# untitled.net
KiCad netlist of a schematic drawn in EAGLE
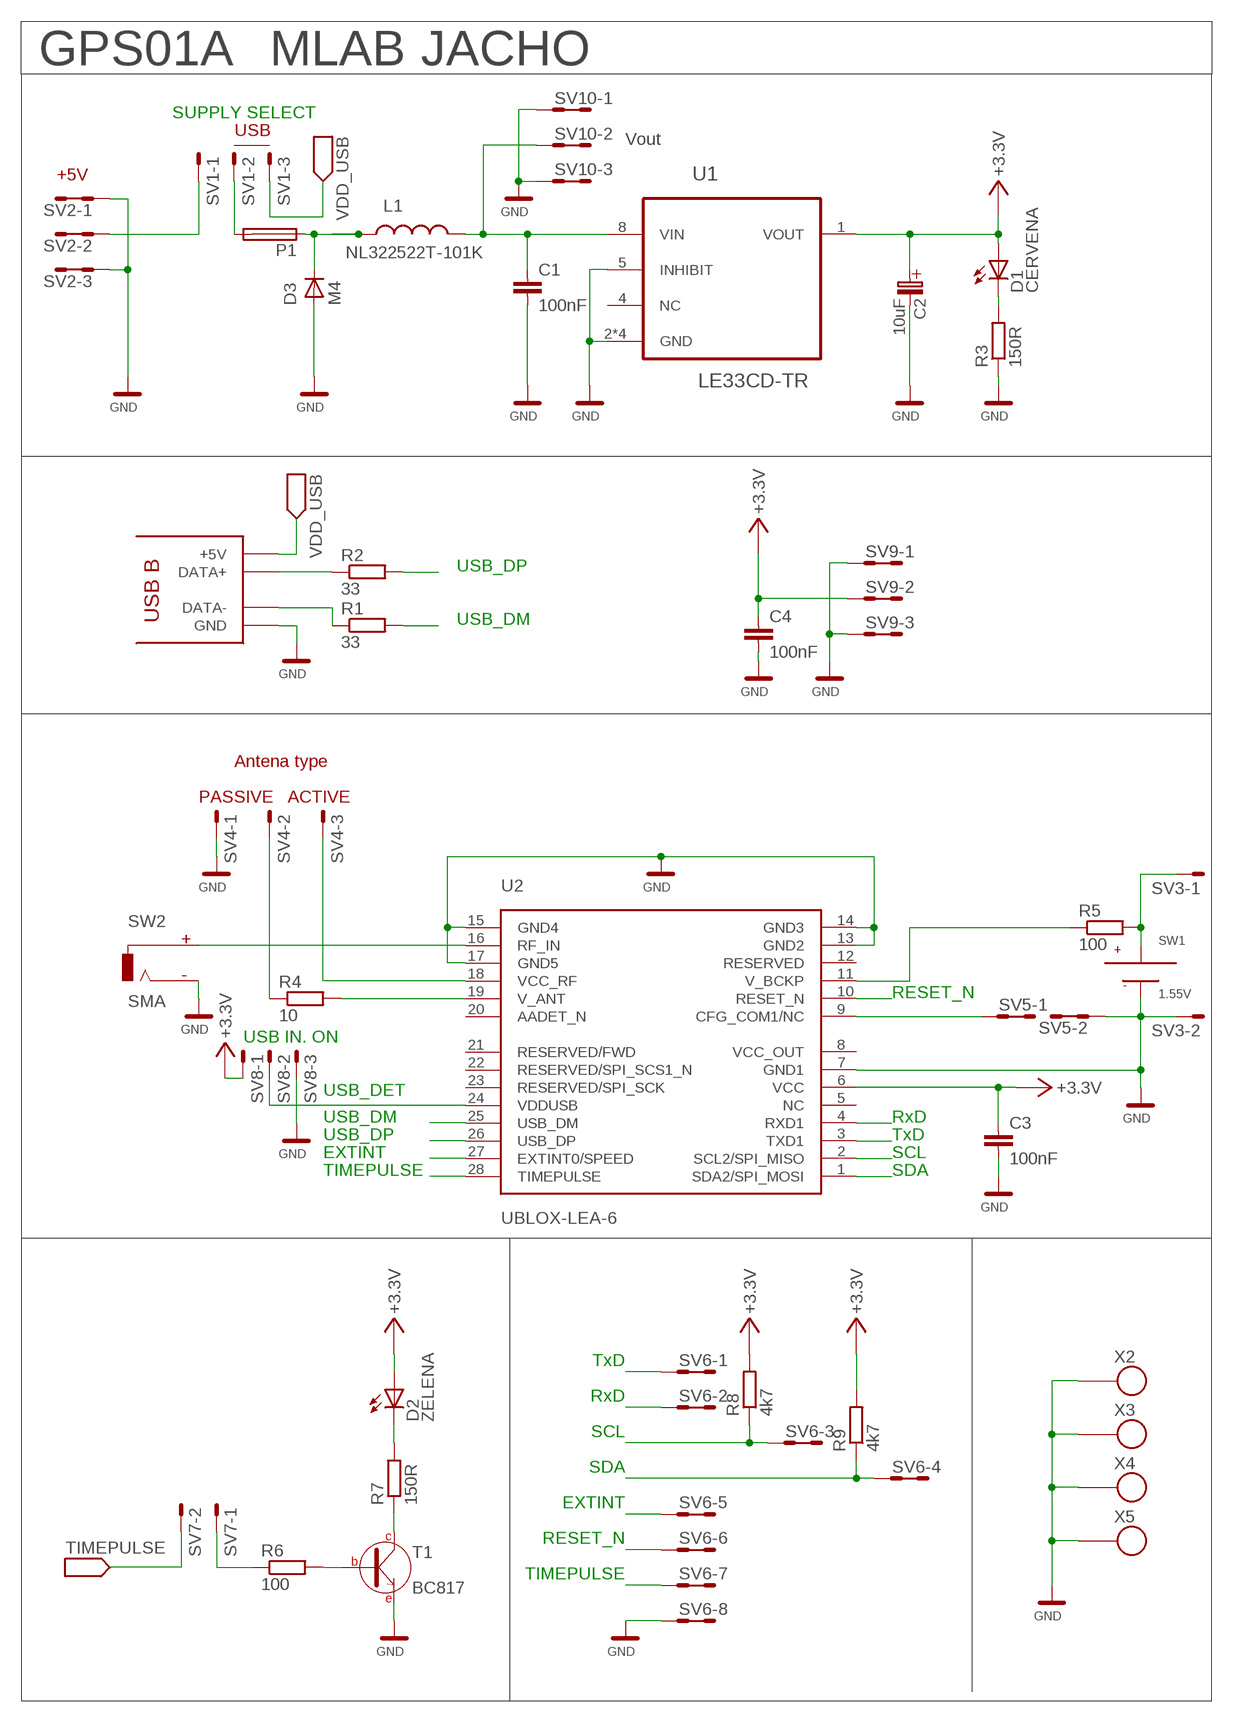
[diagram p0: schematic, sheet 1]

(export (version "E")
  (design (tool "Eeschema 10.0.6"))
  (components
    (comp (ref "C1")
      (value "100nF")
      (footprint "eagle-import:C0805")
      (libsource (lib "eagle-import") (part "C0805"))
    )
    (comp (ref "C2") (value "10uF") (footprint "eagle-import:B") (libsource (lib "eagle-import") (part "B")))
    (comp (ref "C3")
      (value "100nF")
      (footprint "eagle-import:C0805")
      (libsource (lib "eagle-import") (part "C0805"))
    )
    (comp (ref "C4")
      (value "100nF")
      (footprint "eagle-import:C0805")
      (libsource (lib "eagle-import") (part "C0805"))
    )
    (comp (ref "D1")
      (value "CERVENA")
      (footprint "eagle-import:1206")
      (libsource (lib "eagle-import") (part "LED1206"))
    )
    (comp (ref "D2")
      (value "ZELENA")
      (footprint "eagle-import:1206")
      (libsource (lib "eagle-import") (part "LED1206"))
    )
    (comp (ref "D3")
      (value "M4")
      (footprint "eagle-import:SMA")
      (libsource (lib "eagle-import") (part "D-OB.SMA"))
    )
    (comp (ref "L1")
      (value "NL322522T-101K")
      (footprint "eagle-import:1210")
      (libsource (lib "eagle-import") (part "L1210"))
    )
    (comp (ref "P1")
      (value "POJISTKA_1812")
      (footprint "eagle-import:1812")
      (libsource (lib "eagle-import") (part "POJISTKA_1812"))
    )
    (comp (ref "R1")
      (value "33")
      (footprint "eagle-import:0805")
      (libsource (lib "eagle-import") (part "R0805"))
    )
    (comp (ref "R2")
      (value "33")
      (footprint "eagle-import:0805")
      (libsource (lib "eagle-import") (part "R0805"))
    )
    (comp (ref "R3")
      (value "150R")
      (footprint "eagle-import:0805")
      (libsource (lib "eagle-import") (part "R0805"))
    )
    (comp (ref "R4")
      (value "10")
      (footprint "eagle-import:0805")
      (libsource (lib "eagle-import") (part "R0805"))
    )
    (comp (ref "R5")
      (value "100")
      (footprint "eagle-import:0805")
      (libsource (lib "eagle-import") (part "R0805"))
    )
    (comp (ref "R6")
      (value "100")
      (footprint "eagle-import:0805")
      (libsource (lib "eagle-import") (part "R0805"))
    )
    (comp (ref "R7")
      (value "150R")
      (footprint "eagle-import:0805")
      (libsource (lib "eagle-import") (part "R0805"))
    )
    (comp (ref "R8")
      (value "4k7")
      (footprint "eagle-import:0805")
      (libsource (lib "eagle-import") (part "R0805"))
    )
    (comp (ref "R9")
      (value "4k7")
      (footprint "eagle-import:0805")
      (libsource (lib "eagle-import") (part "R0805"))
    )
    (comp (ref "SV1")
      (value "MA03-1")
      (footprint "eagle-import:MA03-1")
      (libsource (lib "eagle-import") (part "MA03-1"))
    )
    (comp (ref "SV2")
      (value "MA03-2")
      (footprint "eagle-import:MA03-2")
      (libsource (lib "eagle-import") (part "MA03-2"))
    )
    (comp (ref "SV3")
      (value "MA02-1")
      (footprint "eagle-import:MA02-1")
      (libsource (lib "eagle-import") (part "MA02-1"))
    )
    (comp (ref "SV4")
      (value "MA03-1")
      (footprint "eagle-import:MA03-1")
      (libsource (lib "eagle-import") (part "MA03-1"))
    )
    (comp (ref "SV5")
      (value "MA02-2")
      (footprint "eagle-import:MA02-2")
      (libsource (lib "eagle-import") (part "MA02-2"))
    )
    (comp (ref "SV6")
      (value "MA08-2")
      (footprint "eagle-import:MA08-2")
      (libsource (lib "eagle-import") (part "MA08-2"))
    )
    (comp (ref "SV7")
      (value "MA02-1")
      (footprint "eagle-import:MA02-1")
      (libsource (lib "eagle-import") (part "MA02-1"))
    )
    (comp (ref "SV8")
      (value "MA03-1")
      (footprint "eagle-import:MA03-1")
      (libsource (lib "eagle-import") (part "MA03-1"))
    )
    (comp (ref "SV9")
      (value "MA03-2")
      (footprint "eagle-import:MA03-2")
      (libsource (lib "eagle-import") (part "MA03-2"))
    )
    (comp (ref "SV10")
      (value "MA03-2")
      (footprint "eagle-import:MA03-2")
      (libsource (lib "eagle-import") (part "MA03-2"))
    )
    (comp (ref "SW1")
      (value "1.55V")
      (footprint "eagle-import:BAT6MM8")
      (libsource (lib "eagle-import") (part "BAT6MM8"))
    )
    (comp (ref "SW2")
      (value "SMA")
      (footprint "eagle-import:SMA")
      (libsource (lib "eagle-import") (part "SMA"))
    )
    (comp (ref "T1")
      (value "BC817")
      (footprint "eagle-import:SOT23")
      (libsource (lib "eagle-import") (part "BC817"))
    )
    (comp (ref "U1")
      (value "LE33CD-TR")
      (footprint "eagle-import:SOIC127P600X175-8N")
      (libsource (lib "eagle-import") (part "LE33CD-TR"))
    )
    (comp (ref "U2")
      (value "UBLOX-LEA-6")
      (footprint "eagle-import:UBLOX-LEA-6")
      (libsource (lib "eagle-import") (part "UBLOX-LEA-6"))
    )
    (comp (ref "X1")
      (value "USB_B")
      (footprint "eagle-import:USB_B")
      (libsource (lib "eagle-import") (part "USB_B"))
    )
    (comp (ref "X2")
      (value "SROUB3M")
      (footprint "eagle-import:SROUB3M")
      (libsource (lib "eagle-import") (part "SROUB3M"))
    )
    (comp (ref "X3")
      (value "SROUB3M")
      (footprint "eagle-import:SROUB3M")
      (libsource (lib "eagle-import") (part "SROUB3M"))
    )
    (comp (ref "X4")
      (value "SROUB3M")
      (footprint "eagle-import:SROUB3M")
      (libsource (lib "eagle-import") (part "SROUB3M"))
    )
    (comp (ref "X5")
      (value "SROUB3M")
      (footprint "eagle-import:SROUB3M")
      (libsource (lib "eagle-import") (part "SROUB3M"))
    )
  )
  (nets
    (net (code "1") (name "+3.3V") (class "Default")
      (node (ref "C2") (pin "+") (pinfunction "C_EL+_+") (pintype "passive"))
      (node (ref "C3") (pin "1") (pinfunction "1_1") (pintype "passive"))
      (node (ref "C4") (pin "1") (pinfunction "1_1") (pintype "passive"))
      (node (ref "D1") (pin "A") (pinfunction "A_A") (pintype "passive"))
      (node (ref "D2") (pin "A") (pinfunction "A_A") (pintype "passive"))
      (node (ref "R8") (pin "2") (pinfunction "2_2") (pintype "passive"))
      (node (ref "R9") (pin "2") (pinfunction "2_2") (pintype "passive"))
      (node (ref "SV8") (pin "1") (pinfunction "P$1_1") (pintype "passive"))
      (node (ref "SV9") (pin "3") (pinfunction "K_3") (pintype "passive"))
      (node (ref "SV9") (pin "4") (pinfunction "K_4") (pintype "passive"))
      (node (ref "U1") (pin "1") (pinfunction "VOUT_1") (pintype "output"))
      (node (ref "U2") (pin "6") (pinfunction "VCC_6") (pintype "bidirectional"))
    )
    (net (code "2") (name "/EXTINT") (class "Default")
      (node (ref "SV6") (pin "10") (pinfunction "K_10") (pintype "passive"))
      (node (ref "SV6") (pin "9") (pinfunction "K_9") (pintype "passive"))
      (node (ref "U2") (pin "27") (pinfunction "EXTINT0/SPEED_27") (pintype "bidirectional"))
    )
    (net (code "3") (name "/RESET_N") (class "Default")
      (node (ref "SV6") (pin "11") (pinfunction "K_11") (pintype "passive"))
      (node (ref "SV6") (pin "12") (pinfunction "K_12") (pintype "passive"))
      (node (ref "U2") (pin "10") (pinfunction "RESET_N_10") (pintype "bidirectional"))
    )
    (net (code "4") (name "/RXD") (class "Default")
      (node (ref "SV6") (pin "3") (pinfunction "K_3") (pintype "passive"))
      (node (ref "SV6") (pin "4") (pinfunction "K_4") (pintype "passive"))
      (node (ref "U2") (pin "4") (pinfunction "RXD1_4") (pintype "bidirectional"))
    )
    (net (code "5") (name "/SCL") (class "Default")
      (node (ref "R8") (pin "1") (pinfunction "1_1") (pintype "passive"))
      (node (ref "SV6") (pin "5") (pinfunction "K_5") (pintype "passive"))
      (node (ref "SV6") (pin "6") (pinfunction "K_6") (pintype "passive"))
      (node (ref "U2") (pin "2") (pinfunction "SCL2/SPI_MISO_2") (pintype "bidirectional"))
    )
    (net (code "6") (name "/SDA") (class "Default")
      (node (ref "R9") (pin "1") (pinfunction "1_1") (pintype "passive"))
      (node (ref "SV6") (pin "7") (pinfunction "K_7") (pintype "passive"))
      (node (ref "SV6") (pin "8") (pinfunction "K_8") (pintype "passive"))
      (node (ref "U2") (pin "1") (pinfunction "SDA2/SPI_MOSI_1") (pintype "bidirectional"))
    )
    (net (code "7") (name "/TIMEPULSE") (class "Default")
      (node (ref "SV6") (pin "13") (pinfunction "K_13") (pintype "passive"))
      (node (ref "SV6") (pin "14") (pinfunction "K_14") (pintype "passive"))
      (node (ref "SV7") (pin "2") (pinfunction "P$1_2") (pintype "passive"))
      (node (ref "U2") (pin "28") (pinfunction "TIMEPULSE_28") (pintype "bidirectional"))
    )
    (net (code "8") (name "/TXD") (class "Default")
      (node (ref "SV6") (pin "1") (pinfunction "K_1") (pintype "passive"))
      (node (ref "SV6") (pin "2") (pinfunction "K_2") (pintype "passive"))
      (node (ref "U2") (pin "3") (pinfunction "TXD1_3") (pintype "bidirectional"))
    )
    (net (code "9") (name "/USB_DM") (class "Default")
      (node (ref "R1") (pin "2") (pinfunction "2_2") (pintype "passive"))
      (node (ref "U2") (pin "25") (pinfunction "USB_DM_25") (pintype "bidirectional"))
    )
    (net (code "10") (name "/USB_DP") (class "Default")
      (node (ref "R2") (pin "2") (pinfunction "2_2") (pintype "passive"))
      (node (ref "U2") (pin "26") (pinfunction "USB_DP_26") (pintype "bidirectional"))
    )
    (net (code "11") (name "/VDD_USB") (class "Default")
      (node (ref "SV1") (pin "3") (pinfunction "P$1_3") (pintype "passive"))
      (node (ref "X1") (pin "1") (pinfunction "+5V_1") (pintype "bidirectional"))
    )
    (net (code "12") (name "GND") (class "Default")
      (node (ref "C1") (pin "2") (pinfunction "2_2") (pintype "passive"))
      (node (ref "C2") (pin "-") (pinfunction "C_EL-_-") (pintype "passive"))
      (node (ref "C3") (pin "2") (pinfunction "2_2") (pintype "passive"))
      (node (ref "C4") (pin "2") (pinfunction "2_2") (pintype "passive"))
      (node (ref "D3") (pin "A") (pinfunction "A_A") (pintype "passive"))
      (node (ref "R3") (pin "1") (pinfunction "1_1") (pintype "passive"))
      (node (ref "SV10") (pin "1") (pinfunction "K_1") (pintype "passive"))
      (node (ref "SV10") (pin "2") (pinfunction "K_2") (pintype "passive"))
      (node (ref "SV10") (pin "5") (pinfunction "K_5") (pintype "passive"))
      (node (ref "SV10") (pin "6") (pinfunction "K_6") (pintype "passive"))
      (node (ref "SV2") (pin "1") (pinfunction "K_1") (pintype "passive"))
      (node (ref "SV2") (pin "2") (pinfunction "K_2") (pintype "passive"))
      (node (ref "SV2") (pin "5") (pinfunction "K_5") (pintype "passive"))
      (node (ref "SV2") (pin "6") (pinfunction "K_6") (pintype "passive"))
      (node (ref "SV3") (pin "2") (pinfunction "P$1_2") (pintype "passive"))
      (node (ref "SV4") (pin "1") (pinfunction "P$1_1") (pintype "passive"))
      (node (ref "SV5") (pin "3") (pinfunction "K_3") (pintype "passive"))
      (node (ref "SV5") (pin "4") (pinfunction "K_4") (pintype "passive"))
      (node (ref "SV6") (pin "15") (pinfunction "K_15") (pintype "passive"))
      (node (ref "SV6") (pin "16") (pinfunction "K_16") (pintype "passive"))
      (node (ref "SV8") (pin "3") (pinfunction "P$1_3") (pintype "passive"))
      (node (ref "SV9") (pin "1") (pinfunction "K_1") (pintype "passive"))
      (node (ref "SV9") (pin "2") (pinfunction "K_2") (pintype "passive"))
      (node (ref "SV9") (pin "5") (pinfunction "K_5") (pintype "passive"))
      (node (ref "SV9") (pin "6") (pinfunction "K_6") (pintype "passive"))
      (node (ref "SW1") (pin "-") (pinfunction "-_-") (pintype "passive"))
      (node (ref "SW2") (pin "-1") (pinfunction "-_-1") (pintype "passive"))
      (node (ref "SW2") (pin "-2") (pinfunction "-_-2") (pintype "passive"))
      (node (ref "SW2") (pin "-3") (pinfunction "-_-3") (pintype "passive"))
      (node (ref "SW2") (pin "-4") (pinfunction "-_-4") (pintype "passive"))
      (node (ref "T1") (pin "2") (pinfunction "E_2") (pintype "passive"))
      (node (ref "U1") (pin "2") (pinfunction "GND_2") (pintype "passive"))
      (node (ref "U1") (pin "3") (pinfunction "GND_3") (pintype "passive"))
      (node (ref "U1") (pin "5") (pinfunction "INHIBIT_5") (pintype "passive"))
      (node (ref "U1") (pin "6") (pinfunction "GND_6") (pintype "passive"))
      (node (ref "U1") (pin "7") (pinfunction "GND_7") (pintype "passive"))
      (node (ref "U2") (pin "13") (pinfunction "GND2_13") (pintype "bidirectional"))
      (node (ref "U2") (pin "14") (pinfunction "GND3_14") (pintype "bidirectional"))
      (node (ref "U2") (pin "15") (pinfunction "GND4_15") (pintype "bidirectional"))
      (node (ref "U2") (pin "17") (pinfunction "GND5_17") (pintype "bidirectional"))
      (node (ref "U2") (pin "7") (pinfunction "GND1_7") (pintype "bidirectional"))
      (node (ref "X1") (pin "4") (pinfunction "GND_4") (pintype "bidirectional"))
      (node (ref "X1") (pin "GND") (pinfunction "GND_GND") (pintype "bidirectional"))
      (node (ref "X1") (pin "GND2") (pinfunction "GND_GND2") (pintype "bidirectional"))
      (node (ref "X2") (pin "P$1") (pinfunction "P$1_P$1") (pintype "bidirectional"))
      (node (ref "X3") (pin "P$1") (pinfunction "P$1_P$1") (pintype "bidirectional"))
      (node (ref "X4") (pin "P$1") (pinfunction "P$1_P$1") (pintype "bidirectional"))
      (node (ref "X5") (pin "P$1") (pinfunction "P$1_P$1") (pintype "bidirectional"))
    )
    (net (code "13") (name "Net-(D1-C)") (class "Default")
      (node (ref "D1") (pin "K") (pinfunction "C_K") (pintype "passive"))
      (node (ref "R3") (pin "2") (pinfunction "2_2") (pintype "passive"))
    )
    (net (code "14") (name "Net-(D2-C)") (class "Default")
      (node (ref "D2") (pin "K") (pinfunction "C_K") (pintype "passive"))
      (node (ref "R7") (pin "2") (pinfunction "2_2") (pintype "passive"))
    )
    (net (code "15") (name "Net-(D3-C)") (class "Default")
      (node (ref "D3") (pin "K") (pinfunction "C_K") (pintype "passive"))
      (node (ref "L1") (pin "P$1") (pinfunction "1_P$1") (pintype "passive"))
      (node (ref "P1") (pin "1") (pinfunction "1_1") (pintype "passive"))
    )
    (net (code "16") (name "Net-(L1-2)") (class "Default")
      (node (ref "C1") (pin "1") (pinfunction "1_1") (pintype "passive"))
      (node (ref "L1") (pin "P$2") (pinfunction "2_P$2") (pintype "passive"))
      (node (ref "SV10") (pin "3") (pinfunction "K_3") (pintype "passive"))
      (node (ref "SV10") (pin "4") (pinfunction "K_4") (pintype "passive"))
      (node (ref "U1") (pin "8") (pinfunction "VIN_8") (pintype "power_in"))
    )
    (net (code "17") (name "Net-(SV1A-P$1)") (class "Default")
      (node (ref "SV1") (pin "1") (pinfunction "P$1_1") (pintype "passive"))
      (node (ref "SV2") (pin "3") (pinfunction "K_3") (pintype "passive"))
      (node (ref "SV2") (pin "4") (pinfunction "K_4") (pintype "passive"))
    )
    (net (code "18") (name "Net-(SV1B-P$1)") (class "Default")
      (node (ref "P1") (pin "2") (pinfunction "2_2") (pintype "passive"))
      (node (ref "SV1") (pin "2") (pinfunction "P$1_2") (pintype "passive"))
    )
    (net (code "19") (name "Net-(SV3A-P$1)") (class "Default")
      (node (ref "R5") (pin "2") (pinfunction "2_2") (pintype "passive"))
      (node (ref "SV3") (pin "1") (pinfunction "P$1_1") (pintype "passive"))
      (node (ref "SW1") (pin "1+") (pinfunction "+_1+") (pintype "passive"))
      (node (ref "SW1") (pin "2+") (pinfunction "+_2+") (pintype "passive"))
    )
    (net (code "20") (name "Net-(SV4B-P$1)") (class "Default")
      (node (ref "R4") (pin "1") (pinfunction "1_1") (pintype "passive"))
      (node (ref "SV4") (pin "2") (pinfunction "P$1_2") (pintype "passive"))
    )
    (net (code "21") (name "Net-(SV4C-P$1)") (class "Default")
      (node (ref "SV4") (pin "3") (pinfunction "P$1_3") (pintype "passive"))
      (node (ref "U2") (pin "18") (pinfunction "VCC_RF_18") (pintype "bidirectional"))
    )
    (net (code "22") (name "Net-(SV7A-P$1)") (class "Default")
      (node (ref "R6") (pin "1") (pinfunction "1_1") (pintype "passive"))
      (node (ref "SV7") (pin "1") (pinfunction "P$1_1") (pintype "passive"))
    )
    (net (code "23") (name "Net-(SV8B-P$1)") (class "Default")
      (node (ref "SV8") (pin "2") (pinfunction "P$1_2") (pintype "passive"))
      (node (ref "U2") (pin "24") (pinfunction "VDDUSB_24") (pintype "bidirectional"))
    )
    (net (code "24") (name "Net-(T1-B)") (class "Default")
      (node (ref "R6") (pin "2") (pinfunction "2_2") (pintype "passive"))
      (node (ref "T1") (pin "1") (pinfunction "B_1") (pintype "passive"))
    )
    (net (code "25") (name "Net-(T1-C)") (class "Default")
      (node (ref "R7") (pin "1") (pinfunction "1_1") (pintype "passive"))
      (node (ref "T1") (pin "3") (pinfunction "C_3") (pintype "passive"))
    )
    (net (code "26") (name "Net-(U2-CFG_COM1{slash}NC)") (class "Default")
      (node (ref "SV5") (pin "1") (pinfunction "K_1") (pintype "passive"))
      (node (ref "SV5") (pin "2") (pinfunction "K_2") (pintype "passive"))
      (node (ref "U2") (pin "9") (pinfunction "CFG_COM1/NC_9") (pintype "bidirectional"))
    )
    (net (code "27") (name "Net-(U2-RF_IN)") (class "Default")
      (node (ref "SW2") (pin "+") (pinfunction "+_+") (pintype "passive"))
      (node (ref "U2") (pin "16") (pinfunction "RF_IN_16") (pintype "bidirectional"))
    )
    (net (code "28") (name "Net-(U2-V_ANT)") (class "Default")
      (node (ref "R4") (pin "2") (pinfunction "2_2") (pintype "passive"))
      (node (ref "U2") (pin "19") (pinfunction "V_ANT_19") (pintype "bidirectional"))
    )
    (net (code "29") (name "Net-(U2-V_BCKP)") (class "Default")
      (node (ref "R5") (pin "1") (pinfunction "1_1") (pintype "passive"))
      (node (ref "U2") (pin "11") (pinfunction "V_BCKP_11") (pintype "bidirectional"))
    )
    (net (code "30") (name "Net-(X1-DATA+)") (class "Default")
      (node (ref "R2") (pin "1") (pinfunction "1_1") (pintype "passive"))
      (node (ref "X1") (pin "3") (pinfunction "DATA+_3") (pintype "bidirectional"))
    )
    (net (code "31") (name "Net-(X1-DATA-)") (class "Default")
      (node (ref "R1") (pin "1") (pinfunction "1_1") (pintype "passive"))
      (node (ref "X1") (pin "2") (pinfunction "DATA-_2") (pintype "bidirectional"))
    )
    (net (code "32") (name "unconnected-(U1-NC-Pad4)") (class "Default")
      (node (ref "U1") (pin "4") (pinfunction "NC_4") (pintype "no_connect"))
    )
    (net (code "33") (name "unconnected-(U2-AADET_N-Pad20)") (class "Default")
      (node (ref "U2") (pin "20") (pinfunction "AADET_N_20") (pintype "bidirectional"))
    )
    (net (code "34") (name "unconnected-(U2-NC-Pad5)") (class "Default")
      (node (ref "U2") (pin "5") (pinfunction "NC_5") (pintype "bidirectional"))
    )
    (net (code "35") (name "unconnected-(U2-RESERVED-Pad12)") (class "Default")
      (node (ref "U2") (pin "12") (pinfunction "RESERVED_12") (pintype "bidirectional"))
    )
    (net (code "36") (name "unconnected-(U2-RESERVED{slash}FWD-Pad21)") (class "Default")
      (node (ref "U2") (pin "21") (pinfunction "RESERVED/FWD_21") (pintype "bidirectional"))
    )
    (net (code "37") (name "unconnected-(U2-RESERVED{slash}SPI_SCK-Pad23)") (class "Default")
      (node (ref "U2") (pin "23") (pinfunction "RESERVED/SPI_SCK_23") (pintype "bidirectional"))
    )
    (net (code "38") (name "unconnected-(U2-RESERVED{slash}SPI_SCS1_N-Pad22)") (class "Default")
      (node (ref "U2") (pin "22") (pinfunction "RESERVED/SPI_SCS1_N_22") (pintype "bidirectional"))
    )
    (net (code "39") (name "unconnected-(U2-VCC_OUT-Pad8)") (class "Default")
      (node (ref "U2") (pin "8") (pinfunction "VCC_OUT_8") (pintype "bidirectional"))
    )
  )
)
